# Grove-Base-for-ESPr-Developer.net
KiCad netlist of a schematic drawn in EAGLE
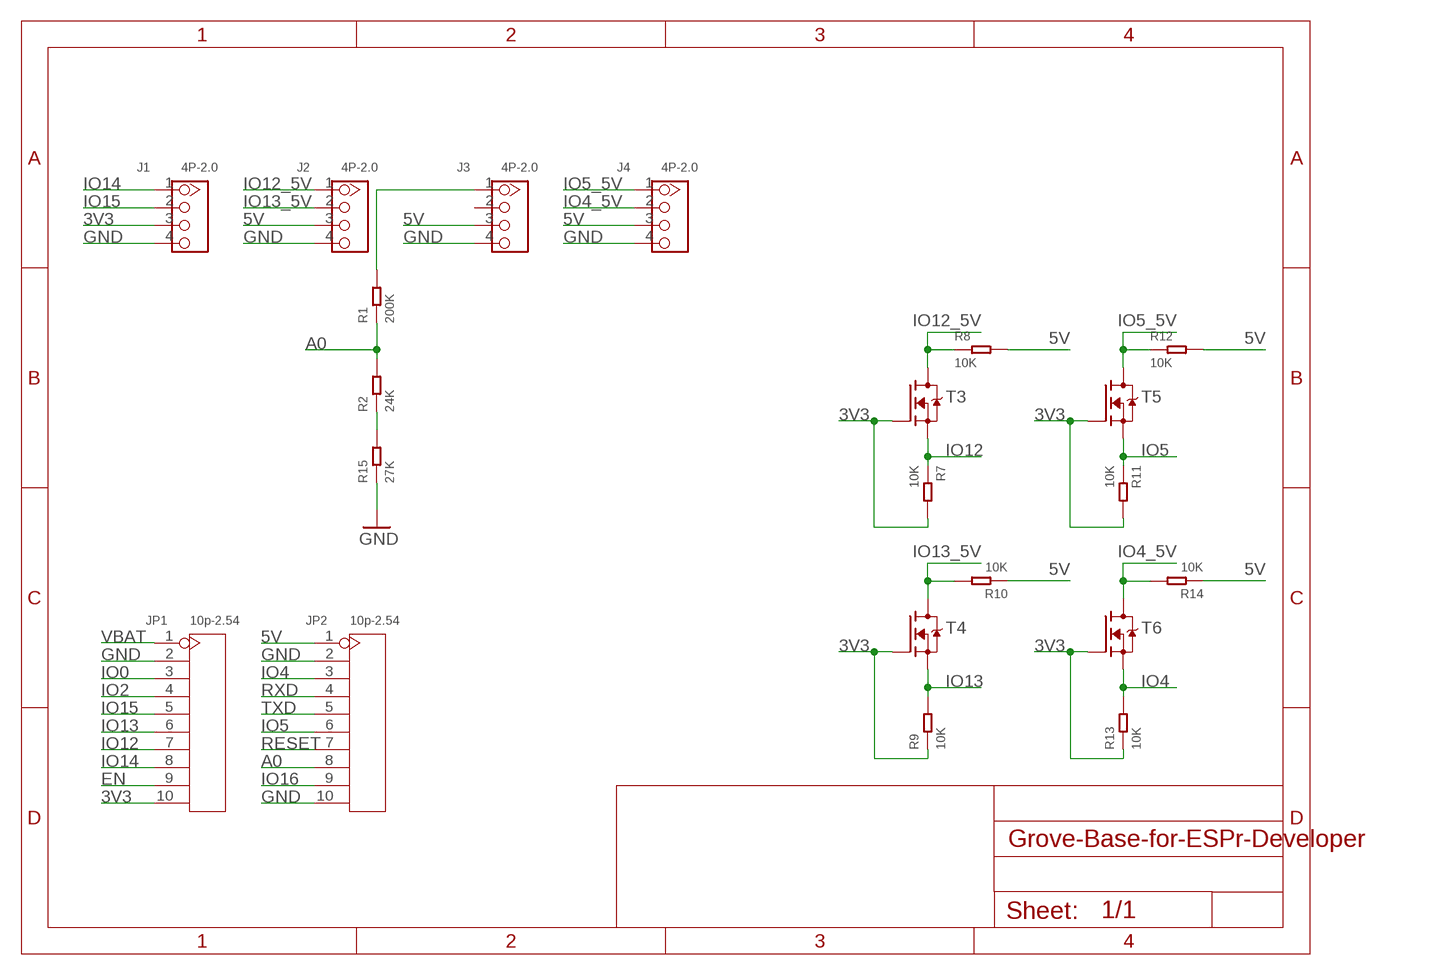
[diagram p0: schematic, sheet 1]

(export (version "E")
  (design (tool "Eeschema 10.0.6"))
  (components
    (comp (ref "J1")
      (value "4P-2.0")
      (footprint "eagle-import:HW4-2.0")
      (libsource (lib "eagle-import") (part "GROVE-CONNECTOR-DIP(4P-2.0)"))
    )
    (comp (ref "J2")
      (value "4P-2.0")
      (footprint "eagle-import:HW4-2.0")
      (libsource (lib "eagle-import") (part "GROVE-CONNECTOR-DIP(4P-2.0)"))
    )
    (comp (ref "J3")
      (value "4P-2.0")
      (footprint "eagle-import:HW4-2.0")
      (libsource (lib "eagle-import") (part "GROVE-CONNECTOR-DIP(4P-2.0)"))
    )
    (comp (ref "J4")
      (value "4P-2.0")
      (footprint "eagle-import:HW4-2.0")
      (libsource (lib "eagle-import") (part "GROVE-CONNECTOR-DIP(4P-2.0)"))
    )
    (comp (ref "JP1")
      (value "10p-2.54")
      (footprint "eagle-import:H10-2.54")
      (fields (field (name "MPN") "P125-1110A0BS116AX"))
      (libsource (lib "eagle-import") (part "DIP-BLACK-MALE-HEADER-VERT(10P-2.54)"))
    )
    (comp (ref "JP2")
      (value "10p-2.54")
      (footprint "eagle-import:H10-2.54")
      (fields (field (name "MPN") "P125-1110A0BS116AX"))
      (libsource (lib "eagle-import") (part "DIP-BLACK-MALE-HEADER-VERT(10P-2.54)"))
    )
    (comp (ref "R1")
      (value "200K")
      (footprint "eagle-import:R0603")
      (fields (field (name "MPN") "RC0603FR-07220KL"))
      (libsource (lib "eagle-import") (part "SMD-RES-220K-1%-1/10W(0603)"))
    )
    (comp (ref "R2")
      (value "24K")
      (footprint "eagle-import:R0603")
      (fields (field (name "MPN") "RC0603FR-07100KL"))
      (libsource (lib "eagle-import") (part "SMD-RES-100K-1%-1/10W(0603)"))
    )
    (comp (ref "R7")
      (value "10K")
      (footprint "eagle-import:R0603")
      (fields (field (name "MPN") "RC0603FR-07220KL"))
      (libsource (lib "eagle-import") (part "SMD-RES-220K-1%-1/10W(0603)"))
    )
    (comp (ref "R8")
      (value "10K")
      (footprint "eagle-import:R0603")
      (fields (field (name "MPN") "RC0603FR-07220KL"))
      (libsource (lib "eagle-import") (part "SMD-RES-220K-1%-1/10W(0603)"))
    )
    (comp (ref "R9")
      (value "10K")
      (footprint "eagle-import:R0603")
      (fields (field (name "MPN") "RC0603FR-07220KL"))
      (libsource (lib "eagle-import") (part "SMD-RES-220K-1%-1/10W(0603)"))
    )
    (comp (ref "R10")
      (value "10K")
      (footprint "eagle-import:R0603")
      (fields (field (name "MPN") "RC0603FR-07220KL"))
      (libsource (lib "eagle-import") (part "SMD-RES-220K-1%-1/10W(0603)"))
    )
    (comp (ref "R11")
      (value "10K")
      (footprint "eagle-import:R0603")
      (fields (field (name "MPN") "RC0603FR-07220KL"))
      (libsource (lib "eagle-import") (part "SMD-RES-220K-1%-1/10W(0603)"))
    )
    (comp (ref "R12")
      (value "10K")
      (footprint "eagle-import:R0603")
      (fields (field (name "MPN") "RC0603FR-07220KL"))
      (libsource (lib "eagle-import") (part "SMD-RES-220K-1%-1/10W(0603)"))
    )
    (comp (ref "R13")
      (value "10K")
      (footprint "eagle-import:R0603")
      (fields (field (name "MPN") "RC0603FR-07220KL"))
      (libsource (lib "eagle-import") (part "SMD-RES-220K-1%-1/10W(0603)"))
    )
    (comp (ref "R14")
      (value "10K")
      (footprint "eagle-import:R0603")
      (fields (field (name "MPN") "RC0603FR-07220KL"))
      (libsource (lib "eagle-import") (part "SMD-RES-220K-1%-1/10W(0603)"))
    )
    (comp (ref "R15")
      (value "27K")
      (footprint "eagle-import:R0603")
      (fields (field (name "MPN") "RC0603FR-07100KL"))
      (libsource (lib "eagle-import") (part "SMD-RES-100K-1%-1/10W(0603)"))
    )
    (comp (ref "T3")
      (value "MOSFET-N-SOT23")
      (footprint "eagle-import:SOT23")
      (libsource (lib "eagle-import") (part "MOSFET-N-SOT23"))
    )
    (comp (ref "T4")
      (value "MOSFET-N-SOT23")
      (footprint "eagle-import:SOT23")
      (libsource (lib "eagle-import") (part "MOSFET-N-SOT23"))
    )
    (comp (ref "T5")
      (value "MOSFET-N-SOT23")
      (footprint "eagle-import:SOT23")
      (libsource (lib "eagle-import") (part "MOSFET-N-SOT23"))
    )
    (comp (ref "T6")
      (value "MOSFET-N-SOT23")
      (footprint "eagle-import:SOT23")
      (libsource (lib "eagle-import") (part "MOSFET-N-SOT23"))
    )
  )
  (nets
    (net (code "1") (name "/3V3") (class "Default")
      (node (ref "J1") (pin "3") (pinfunction "3_3") (pintype "bidirectional"))
      (node (ref "JP1") (pin "10") (pinfunction "10_10") (pintype "bidirectional"))
      (node (ref "R11") (pin "2") (pinfunction "2_2") (pintype "passive"))
      (node (ref "R13") (pin "1") (pinfunction "1_1") (pintype "passive"))
      (node (ref "R7") (pin "2") (pinfunction "2_2") (pintype "passive"))
      (node (ref "R9") (pin "1") (pinfunction "1_1") (pintype "passive"))
      (node (ref "T3") (pin "1") (pinfunction "G_1") (pintype "passive"))
      (node (ref "T4") (pin "1") (pinfunction "G_1") (pintype "passive"))
      (node (ref "T5") (pin "1") (pinfunction "G_1") (pintype "passive"))
      (node (ref "T6") (pin "1") (pinfunction "G_1") (pintype "passive"))
    )
    (net (code "2") (name "/5V") (class "Default")
      (node (ref "J2") (pin "3") (pinfunction "3_3") (pintype "bidirectional"))
      (node (ref "J3") (pin "3") (pinfunction "3_3") (pintype "bidirectional"))
      (node (ref "J4") (pin "3") (pinfunction "3_3") (pintype "bidirectional"))
      (node (ref "JP2") (pin "1") (pinfunction "1_1") (pintype "bidirectional"))
      (node (ref "R10") (pin "1") (pinfunction "1_1") (pintype "passive"))
      (node (ref "R12") (pin "2") (pinfunction "2_2") (pintype "passive"))
      (node (ref "R14") (pin "1") (pinfunction "1_1") (pintype "passive"))
      (node (ref "R8") (pin "2") (pinfunction "2_2") (pintype "passive"))
    )
    (net (code "3") (name "/A0") (class "Default")
      (node (ref "JP2") (pin "8") (pinfunction "8_8") (pintype "bidirectional"))
      (node (ref "R1") (pin "1") (pinfunction "1_1") (pintype "passive"))
      (node (ref "R2") (pin "2") (pinfunction "2_2") (pintype "passive"))
    )
    (net (code "4") (name "/EN") (class "Default")
      (node (ref "JP1") (pin "9") (pinfunction "9_9") (pintype "bidirectional"))
    )
    (net (code "5") (name "/IO0") (class "Default")
      (node (ref "JP1") (pin "3") (pinfunction "3_3") (pintype "bidirectional"))
    )
    (net (code "6") (name "/IO2") (class "Default")
      (node (ref "JP1") (pin "4") (pinfunction "4_4") (pintype "bidirectional"))
    )
    (net (code "7") (name "/IO4") (class "Default")
      (node (ref "JP2") (pin "3") (pinfunction "3_3") (pintype "bidirectional"))
      (node (ref "R13") (pin "2") (pinfunction "2_2") (pintype "passive"))
      (node (ref "T6") (pin "2") (pinfunction "S_2") (pintype "passive"))
    )
    (net (code "8") (name "/IO4_5V") (class "Default")
      (node (ref "J4") (pin "2") (pinfunction "2_2") (pintype "bidirectional"))
      (node (ref "R14") (pin "2") (pinfunction "2_2") (pintype "passive"))
      (node (ref "T6") (pin "3") (pinfunction "D_3") (pintype "passive"))
    )
    (net (code "9") (name "/IO5") (class "Default")
      (node (ref "JP2") (pin "6") (pinfunction "6_6") (pintype "bidirectional"))
      (node (ref "R11") (pin "1") (pinfunction "1_1") (pintype "passive"))
      (node (ref "T5") (pin "2") (pinfunction "S_2") (pintype "passive"))
    )
    (net (code "10") (name "/IO5_5V") (class "Default")
      (node (ref "J4") (pin "1") (pinfunction "1_1") (pintype "bidirectional"))
      (node (ref "R12") (pin "1") (pinfunction "1_1") (pintype "passive"))
      (node (ref "T5") (pin "3") (pinfunction "D_3") (pintype "passive"))
    )
    (net (code "11") (name "/IO12") (class "Default")
      (node (ref "JP1") (pin "7") (pinfunction "7_7") (pintype "bidirectional"))
      (node (ref "R7") (pin "1") (pinfunction "1_1") (pintype "passive"))
      (node (ref "T3") (pin "2") (pinfunction "S_2") (pintype "passive"))
    )
    (net (code "12") (name "/IO12_5V") (class "Default")
      (node (ref "J2") (pin "1") (pinfunction "1_1") (pintype "bidirectional"))
      (node (ref "R8") (pin "1") (pinfunction "1_1") (pintype "passive"))
      (node (ref "T3") (pin "3") (pinfunction "D_3") (pintype "passive"))
    )
    (net (code "13") (name "/IO13") (class "Default")
      (node (ref "JP1") (pin "6") (pinfunction "6_6") (pintype "bidirectional"))
      (node (ref "R9") (pin "2") (pinfunction "2_2") (pintype "passive"))
      (node (ref "T4") (pin "2") (pinfunction "S_2") (pintype "passive"))
    )
    (net (code "14") (name "/IO13_5V") (class "Default")
      (node (ref "J2") (pin "2") (pinfunction "2_2") (pintype "bidirectional"))
      (node (ref "R10") (pin "2") (pinfunction "2_2") (pintype "passive"))
      (node (ref "T4") (pin "3") (pinfunction "D_3") (pintype "passive"))
    )
    (net (code "15") (name "/IO14") (class "Default")
      (node (ref "J1") (pin "1") (pinfunction "1_1") (pintype "bidirectional"))
      (node (ref "JP1") (pin "8") (pinfunction "8_8") (pintype "bidirectional"))
    )
    (net (code "16") (name "/IO15") (class "Default")
      (node (ref "J1") (pin "2") (pinfunction "2_2") (pintype "bidirectional"))
      (node (ref "JP1") (pin "5") (pinfunction "5_5") (pintype "bidirectional"))
    )
    (net (code "17") (name "/IO16") (class "Default")
      (node (ref "JP2") (pin "9") (pinfunction "9_9") (pintype "bidirectional"))
    )
    (net (code "18") (name "/RESET") (class "Default")
      (node (ref "JP2") (pin "7") (pinfunction "7_7") (pintype "bidirectional"))
    )
    (net (code "19") (name "/RXD") (class "Default")
      (node (ref "JP2") (pin "4") (pinfunction "4_4") (pintype "bidirectional"))
    )
    (net (code "20") (name "/TXD") (class "Default")
      (node (ref "JP2") (pin "5") (pinfunction "5_5") (pintype "bidirectional"))
    )
    (net (code "21") (name "/VBAT") (class "Default")
      (node (ref "JP1") (pin "1") (pinfunction "1_1") (pintype "bidirectional"))
    )
    (net (code "22") (name "GND") (class "Default")
      (node (ref "J1") (pin "4") (pinfunction "4_4") (pintype "bidirectional"))
      (node (ref "J2") (pin "4") (pinfunction "4_4") (pintype "bidirectional"))
      (node (ref "J3") (pin "4") (pinfunction "4_4") (pintype "bidirectional"))
      (node (ref "J4") (pin "4") (pinfunction "4_4") (pintype "bidirectional"))
      (node (ref "JP1") (pin "2") (pinfunction "2_2") (pintype "bidirectional"))
      (node (ref "JP2") (pin "10") (pinfunction "10_10") (pintype "bidirectional"))
      (node (ref "JP2") (pin "2") (pinfunction "2_2") (pintype "bidirectional"))
      (node (ref "R15") (pin "1") (pinfunction "1_1") (pintype "passive"))
    )
    (net (code "23") (name "Net-(J3-Pad1)") (class "Default")
      (node (ref "J3") (pin "1") (pinfunction "1_1") (pintype "bidirectional"))
      (node (ref "R1") (pin "2") (pinfunction "2_2") (pintype "passive"))
    )
    (net (code "24") (name "Net-(R15-Pad2)") (class "Default")
      (node (ref "R15") (pin "2") (pinfunction "2_2") (pintype "passive"))
      (node (ref "R2") (pin "1") (pinfunction "1_1") (pintype "passive"))
    )
    (net (code "25") (name "unconnected-(J3-Pad2)") (class "Default")
      (node (ref "J3") (pin "2") (pinfunction "2_2") (pintype "bidirectional"))
    )
  )
)
